# Sheet_1_2022-08-15.net
KiCad netlist of a schematic drawn in Altium Designer
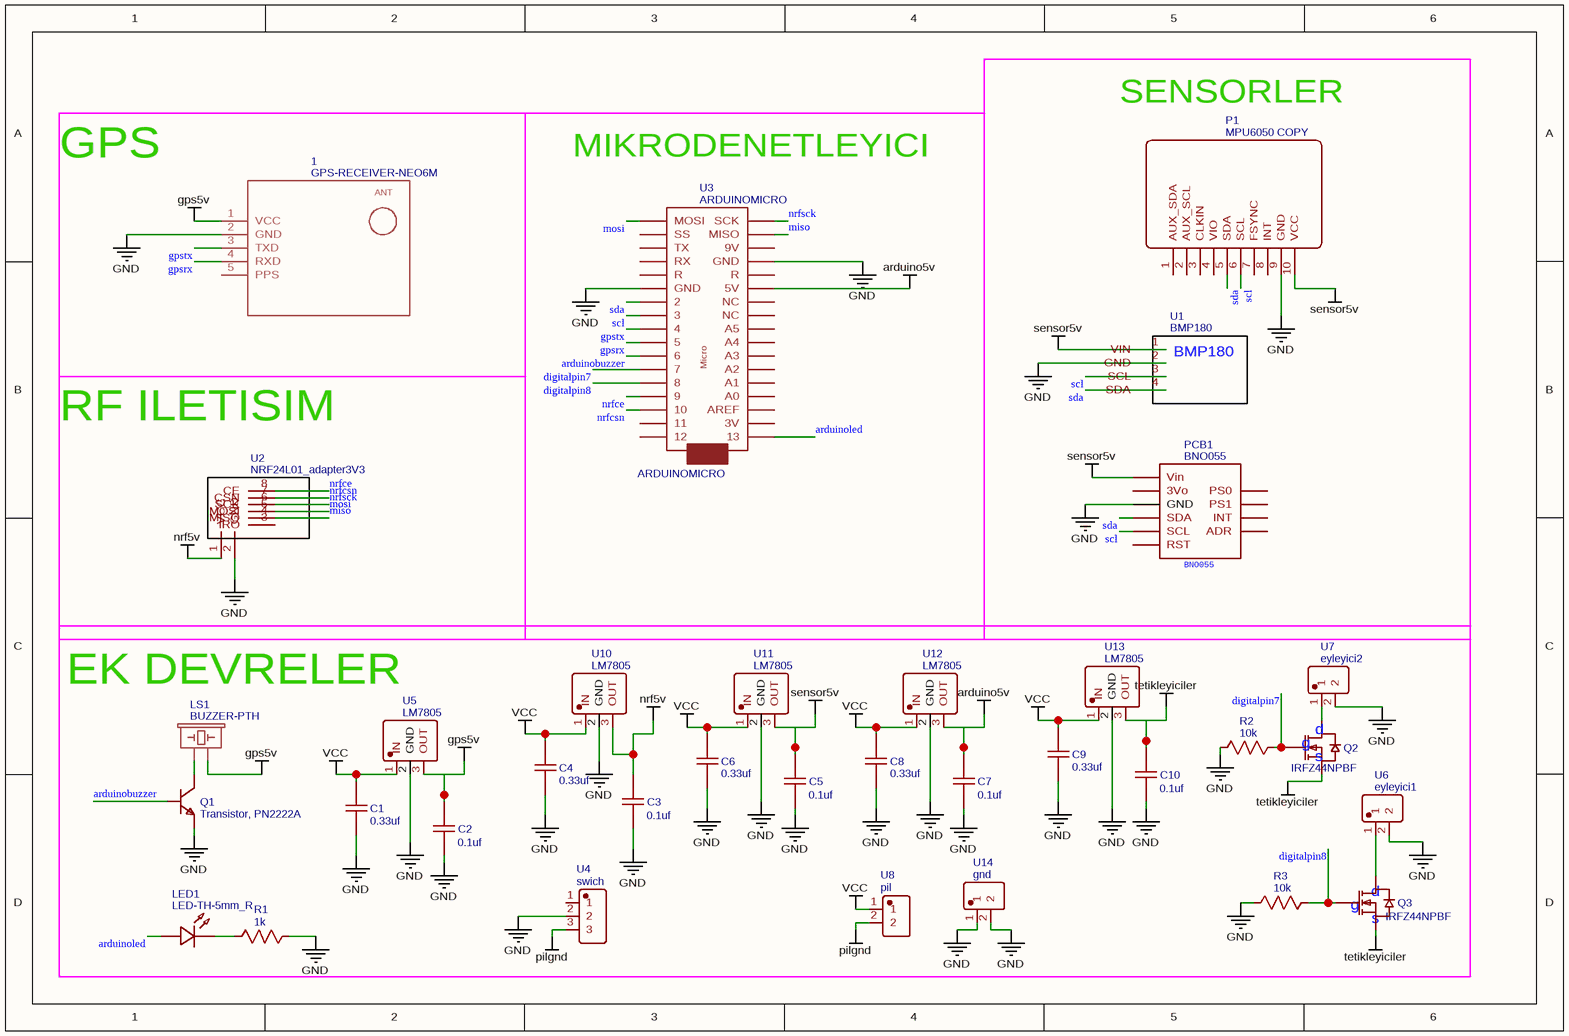
[diagram p0: Sheet_1_2022-08-15.schdoc]

(export (version "E")
  (design (tool "Eeschema 10.0.6"))
  (components
    (comp (ref "1")
      (value "GPS-RECEIVER-NEO6M")
      (fields (field (name "CONTRIBUTOR") "Otto Sonneveld"))
      (libsource (lib "altium-import") (part "root_0_GPS-RECEIVER-NEO6M_"))
    )
    (comp (ref "C1")
      (value "0.33uf")
      (fields (field (name "CONTRIBUTOR") "LCEDA_Lib"))
      (libsource (lib "altium-import") (part "root_1_0.33uf_"))
    )
    (comp (ref "C2")
      (value "0.1uf")
      (fields (field (name "CONTRIBUTOR") "LCEDA_Lib"))
      (libsource (lib "altium-import") (part "root_1_0.1uf_"))
    )
    (comp (ref "C3")
      (value "0.1uf")
      (fields (field (name "CONTRIBUTOR") "LCEDA_Lib"))
      (libsource (lib "altium-import") (part "root_1_0.1uf_"))
    )
    (comp (ref "C4")
      (value "0.33uf")
      (fields (field (name "CONTRIBUTOR") "LCEDA_Lib"))
      (libsource (lib "altium-import") (part "root_1_0.33uf_"))
    )
    (comp (ref "C5")
      (value "0.1uf")
      (fields (field (name "CONTRIBUTOR") "LCEDA_Lib"))
      (libsource (lib "altium-import") (part "root_1_0.1uf_"))
    )
    (comp (ref "C6")
      (value "0.33uf")
      (fields (field (name "CONTRIBUTOR") "LCEDA_Lib"))
      (libsource (lib "altium-import") (part "root_1_0.33uf_"))
    )
    (comp (ref "C7")
      (value "0.1uf")
      (fields (field (name "CONTRIBUTOR") "LCEDA_Lib"))
      (libsource (lib "altium-import") (part "root_1_0.1uf_"))
    )
    (comp (ref "C8")
      (value "0.33uf")
      (fields (field (name "CONTRIBUTOR") "LCEDA_Lib"))
      (libsource (lib "altium-import") (part "root_1_0.33uf_"))
    )
    (comp (ref "C9")
      (value "0.33uf")
      (fields (field (name "CONTRIBUTOR") "LCEDA_Lib"))
      (libsource (lib "altium-import") (part "root_1_0.33uf_"))
    )
    (comp (ref "C10")
      (value "0.1uf")
      (fields (field (name "CONTRIBUTOR") "LCEDA_Lib"))
      (libsource (lib "altium-import") (part "root_1_0.1uf_"))
    )
    (comp (ref "LED1")
      (value "LED-TH-5mm_R")
      (fields
        (field (name "BOM_MANUFACTURER PART") "333-2SURD/S530-A3")
        (field (name "BOM_SUPPLIER PART") "C87271")
        (field (name "CONTRIBUTOR") "LCEDA_Lib")
      )
      (libsource (lib "altium-import") (part "root_0_LED-TH-5mm_R_"))
    )
    (comp (ref "LS1")
      (value "BUZZER-PTH")
      (fields (field (name "CONTRIBUTOR") "Maxime Djouf"))
      (libsource (lib "altium-import") (part "root_0_BUZZER-PTH_"))
    )
    (comp (ref "P1") (value "MPU6050 COPY") (libsource (lib "altium-import") (part "root_0_MPU6050 COPY_")))
    (comp (ref "PCB1") (value "BNO055") (libsource (lib "altium-import") (part "root_0_BNO055_")))
    (comp (ref "Q1")
      (value "Transistor, PN2222A")
      (fields (field (name "BOM_MANUFACTURER PART") "PN2222A") (field (name "CONTRIBUTOR") "benjamin.nemec"))
      (libsource (lib "altium-import") (part "root_0_Transistor, PN2222A_"))
    )
    (comp (ref "Q2")
      (value "IRFZ44NPBF")
      (fields (field (name "BOM_SUPPLIER PART") "C2586"))
      (libsource (lib "altium-import") (part "root_0_IRFZ44NPBF_"))
    )
    (comp (ref "Q3")
      (value "IRFZ44NPBF")
      (fields (field (name "BOM_SUPPLIER PART") "C2586"))
      (libsource (lib "altium-import") (part "root_0_IRFZ44NPBF_"))
    )
    (comp (ref "R1")
      (value "1k")
      (fields (field (name "CONTRIBUTOR") "LCEDA_Lib"))
      (libsource (lib "altium-import") (part "root_0_1k_"))
    )
    (comp (ref "R2")
      (value "10k")
      (fields (field (name "CONTRIBUTOR") "LCEDA_Lib"))
      (libsource (lib "altium-import") (part "root_0_10k_"))
    )
    (comp (ref "R3")
      (value "10k")
      (fields (field (name "CONTRIBUTOR") "LCEDA_Lib"))
      (libsource (lib "altium-import") (part "root_0_10k_"))
    )
    (comp (ref "U1")
      (value "BMP180")
      (fields (field (name "CONTRIBUTOR") "delil1220"))
      (libsource (lib "altium-import") (part "root_0_BMP180_"))
    )
    (comp (ref "U2")
      (value "NRF24L01_adapter3V3")
      (fields (field (name "CONTRIBUTOR") "boonchuan khongsupsinsiri"))
      (libsource (lib "altium-import") (part "root_0_NRF24L01_adapter3V3_"))
    )
    (comp (ref "U3") (value "ARDUINOMICRO") (libsource (lib "altium-import") (part "root_1_ARDUINOMICRO_")))
    (comp (ref "U4")
      (value "swich")
      (fields (field (name "CONTRIBUTOR") "kenanbatur4"))
      (libsource (lib "altium-import") (part "root_0_swich_"))
    )
    (comp (ref "U5")
      (value "LM7805")
      (fields (field (name "BOM_SUPPLIER PART") "C845394") (field (name "CONTRIBUTOR") "LCSC"))
      (libsource (lib "altium-import") (part "root_1_LM7805_"))
    )
    (comp (ref "U6")
      (value "eyleyici1")
      (fields (field (name "CONTRIBUTOR") "kenanbatur"))
      (libsource (lib "altium-import") (part "root_1_eyleyici1_"))
    )
    (comp (ref "U7")
      (value "eyleyici2")
      (fields (field (name "CONTRIBUTOR") "kenanbatur"))
      (libsource (lib "altium-import") (part "root_1_eyleyici2_"))
    )
    (comp (ref "U8")
      (value "pil")
      (fields (field (name "CONTRIBUTOR") "kenanbatur"))
      (libsource (lib "altium-import") (part "root_0_pil_"))
    )
    (comp (ref "U10")
      (value "LM7805")
      (fields (field (name "BOM_SUPPLIER PART") "C845394") (field (name "CONTRIBUTOR") "LCSC"))
      (libsource (lib "altium-import") (part "root_1_LM7805_"))
    )
    (comp (ref "U11")
      (value "LM7805")
      (fields (field (name "BOM_SUPPLIER PART") "C845394") (field (name "CONTRIBUTOR") "LCSC"))
      (libsource (lib "altium-import") (part "root_1_LM7805_"))
    )
    (comp (ref "U12")
      (value "LM7805")
      (fields (field (name "BOM_SUPPLIER PART") "C845394") (field (name "CONTRIBUTOR") "LCSC"))
      (libsource (lib "altium-import") (part "root_1_LM7805_"))
    )
    (comp (ref "U13")
      (value "LM7805")
      (fields (field (name "BOM_SUPPLIER PART") "C845394") (field (name "CONTRIBUTOR") "LCSC"))
      (libsource (lib "altium-import") (part "root_1_LM7805_"))
    )
    (comp (ref "U14")
      (value "gnd")
      (fields (field (name "CONTRIBUTOR") "kenanbatur"))
      (libsource (lib "altium-import") (part "root_1_gnd_"))
    )
  )
  (nets
    (net (code "1") (name "/arduinobuzzer") (class "Default")
      (node (ref "Q1") (pin "2") (pinfunction "B_2") (pintype "passive"))
      (node (ref "U3") (pin "P$7") (pinfunction "6_P$7") (pintype "passive"))
    )
    (net (code "2") (name "/arduinoled") (class "Default")
      (node (ref "LED1") (pin "1") (pinfunction "1_1") (pintype "passive"))
      (node (ref "U3") (pin "P$34") (pinfunction "13_P$34") (pintype "passive"))
    )
    (net (code "3") (name "/digitalpin7") (class "Default")
      (node (ref "Q2") (pin "1") (pinfunction "G_1") (pintype "passive"))
      (node (ref "R2") (pin "2") (pinfunction "2_2") (pintype "passive"))
      (node (ref "U3") (pin "P$6") (pinfunction "7_P$6") (pintype "passive"))
    )
    (net (code "4") (name "/digitalpin8") (class "Default")
      (node (ref "Q3") (pin "1") (pinfunction "G_1") (pintype "passive"))
      (node (ref "R3") (pin "2") (pinfunction "2_2") (pintype "passive"))
      (node (ref "U3") (pin "P$5") (pinfunction "8_P$5") (pintype "passive"))
    )
    (net (code "5") (name "/gpsrx") (class "Default")
      (node (ref "1") (pin "4") (pinfunction "RXD_4") (pintype "passive"))
      (node (ref "U3") (pin "P$8") (pinfunction "5_P$8") (pintype "passive"))
    )
    (net (code "6") (name "/gpstx") (class "Default")
      (node (ref "1") (pin "3") (pinfunction "TXD_3") (pintype "passive"))
      (node (ref "U3") (pin "P$9") (pinfunction "4_P$9") (pintype "passive"))
    )
    (net (code "7") (name "/miso") (class "Default")
      (node (ref "U2") (pin "4") (pinfunction "MISO_4") (pintype "passive"))
      (node (ref "U3") (pin "P$19") (pinfunction "MISO_P$19") (pintype "passive"))
    )
    (net (code "8") (name "/mosi") (class "Default")
      (node (ref "U2") (pin "5") (pinfunction "MOSI_5") (pintype "passive"))
      (node (ref "U3") (pin "P$17") (pinfunction "MOSI_P$17") (pintype "passive"))
    )
    (net (code "9") (name "/nrfce") (class "Default")
      (node (ref "U2") (pin "8") (pinfunction "CE_8") (pintype "passive"))
      (node (ref "U3") (pin "P$4") (pinfunction "9_P$4") (pintype "passive"))
    )
    (net (code "10") (name "/nrfcsn") (class "Default")
      (node (ref "U2") (pin "7") (pinfunction "CSN_7") (pintype "passive"))
      (node (ref "U3") (pin "P$3") (pinfunction "10_P$3") (pintype "passive"))
    )
    (net (code "11") (name "/nrfsck") (class "Default")
      (node (ref "U2") (pin "6") (pinfunction "SCK_6") (pintype "passive"))
      (node (ref "U3") (pin "P$18") (pinfunction "SCK_P$18") (pintype "passive"))
    )
    (net (code "12") (name "/scl") (class "Default")
      (node (ref "P1") (pin "6") (pinfunction "SCL_6") (pintype "passive"))
      (node (ref "PCB1") (pin "5") (pinfunction "SCL_5") (pintype "passive"))
      (node (ref "U1") (pin "3") (pinfunction "SCL_3") (pintype "passive"))
      (node (ref "U3") (pin "P$10") (pinfunction "3_P$10") (pintype "passive"))
    )
    (net (code "13") (name "/sda") (class "Default")
      (node (ref "P1") (pin "5") (pinfunction "SDA_5") (pintype "passive"))
      (node (ref "PCB1") (pin "4") (pinfunction "SDA_4") (pintype "passive"))
      (node (ref "U1") (pin "4") (pinfunction "SDA_4") (pintype "passive"))
      (node (ref "U3") (pin "P$11") (pinfunction "2_P$11") (pintype "passive"))
    )
    (net (code "14") (name "GND") (class "Default")
      (node (ref "1") (pin "2") (pinfunction "GND_2") (pintype "passive"))
      (node (ref "C1") (pin "1") (pinfunction "1_1") (pintype "passive"))
      (node (ref "C10") (pin "1") (pinfunction "1_1") (pintype "passive"))
      (node (ref "C2") (pin "1") (pinfunction "1_1") (pintype "passive"))
      (node (ref "C3") (pin "1") (pinfunction "1_1") (pintype "passive"))
      (node (ref "C4") (pin "1") (pinfunction "1_1") (pintype "passive"))
      (node (ref "C5") (pin "1") (pinfunction "1_1") (pintype "passive"))
      (node (ref "C6") (pin "1") (pinfunction "1_1") (pintype "passive"))
      (node (ref "C7") (pin "1") (pinfunction "1_1") (pintype "passive"))
      (node (ref "C8") (pin "1") (pinfunction "1_1") (pintype "passive"))
      (node (ref "C9") (pin "1") (pinfunction "1_1") (pintype "passive"))
      (node (ref "P1") (pin "9") (pinfunction "GND_9") (pintype "passive"))
      (node (ref "PCB1") (pin "3") (pinfunction "GND_3") (pintype "passive"))
      (node (ref "Q1") (pin "1") (pinfunction "E_1") (pintype "passive"))
      (node (ref "R1") (pin "2") (pinfunction "2_2") (pintype "passive"))
      (node (ref "R2") (pin "1") (pinfunction "1_1") (pintype "passive"))
      (node (ref "R3") (pin "1") (pinfunction "1_1") (pintype "passive"))
      (node (ref "U1") (pin "2") (pinfunction "GND_2") (pintype "passive"))
      (node (ref "U10") (pin "2") (pinfunction "GND_2") (pintype "passive"))
      (node (ref "U11") (pin "2") (pinfunction "GND_2") (pintype "passive"))
      (node (ref "U12") (pin "2") (pinfunction "GND_2") (pintype "passive"))
      (node (ref "U13") (pin "2") (pinfunction "GND_2") (pintype "passive"))
      (node (ref "U14") (pin "1") (pinfunction "1_1") (pintype "passive"))
      (node (ref "U14") (pin "2") (pinfunction "2_2") (pintype "passive"))
      (node (ref "U2") (pin "2") (pinfunction "GND_2") (pintype "passive"))
      (node (ref "U3") (pin "P$12") (pinfunction "GND_P$12") (pintype "passive"))
      (node (ref "U3") (pin "P$21") (pinfunction "GND_P$21") (pintype "passive"))
      (node (ref "U4") (pin "2") (pinfunction "2_2") (pintype "passive"))
      (node (ref "U5") (pin "2") (pinfunction "GND_2") (pintype "passive"))
      (node (ref "U6") (pin "2") (pinfunction "2_2") (pintype "passive"))
      (node (ref "U7") (pin "2") (pinfunction "2_2") (pintype "passive"))
    )
    (net (code "15") (name "Net-(LED1-Pad2)") (class "Default")
      (node (ref "LED1") (pin "2") (pinfunction "2_2") (pintype "passive"))
      (node (ref "R1") (pin "1") (pinfunction "1_1") (pintype "passive"))
    )
    (net (code "16") (name "Net-(LS1-1)") (class "Default")
      (node (ref "LS1") (pin "+") (pinfunction "1_+") (pintype "passive"))
      (node (ref "Q1") (pin "3") (pinfunction "C_3") (pintype "passive"))
    )
    (net (code "17") (name "Net-(Q2-D)") (class "Default")
      (node (ref "Q2") (pin "2") (pinfunction "D_2") (pintype "passive"))
      (node (ref "U7") (pin "1") (pinfunction "1_1") (pintype "passive"))
    )
    (net (code "18") (name "Net-(Q3-D)") (class "Default")
      (node (ref "Q3") (pin "2") (pinfunction "D_2") (pintype "passive"))
      (node (ref "U6") (pin "1") (pinfunction "1_1") (pintype "passive"))
    )
    (net (code "19") (name "VCC") (class "Default")
      (node (ref "C1") (pin "2") (pinfunction "2_2") (pintype "passive"))
      (node (ref "C4") (pin "2") (pinfunction "2_2") (pintype "passive"))
      (node (ref "C6") (pin "2") (pinfunction "2_2") (pintype "passive"))
      (node (ref "C8") (pin "2") (pinfunction "2_2") (pintype "passive"))
      (node (ref "C9") (pin "2") (pinfunction "2_2") (pintype "passive"))
      (node (ref "U10") (pin "1") (pinfunction "IN_1") (pintype "passive"))
      (node (ref "U11") (pin "1") (pinfunction "IN_1") (pintype "passive"))
      (node (ref "U12") (pin "1") (pinfunction "IN_1") (pintype "passive"))
      (node (ref "U13") (pin "1") (pinfunction "IN_1") (pintype "passive"))
      (node (ref "U5") (pin "1") (pinfunction "IN_1") (pintype "passive"))
      (node (ref "U8") (pin "1") (pinfunction "1_1") (pintype "passive"))
    )
    (net (code "20") (name "arduino5v") (class "Default")
      (node (ref "C7") (pin "2") (pinfunction "2_2") (pintype "passive"))
      (node (ref "U12") (pin "3") (pinfunction "OUT_3") (pintype "passive"))
      (node (ref "U3") (pin "P$23") (pinfunction "5V_P$23") (pintype "passive"))
    )
    (net (code "21") (name "gps5v") (class "Default")
      (node (ref "1") (pin "1") (pinfunction "VCC_1") (pintype "passive"))
      (node (ref "C2") (pin "2") (pinfunction "2_2") (pintype "passive"))
      (node (ref "LS1") (pin "-") (pinfunction "2_-") (pintype "passive"))
      (node (ref "U5") (pin "3") (pinfunction "OUT_3") (pintype "passive"))
    )
    (net (code "22") (name "nrf5v") (class "Default")
      (node (ref "C3") (pin "2") (pinfunction "2_2") (pintype "passive"))
      (node (ref "U10") (pin "3") (pinfunction "OUT_3") (pintype "passive"))
      (node (ref "U2") (pin "1") (pinfunction "VCC_1") (pintype "passive"))
    )
    (net (code "23") (name "pilgnd") (class "Default")
      (node (ref "U4") (pin "3") (pinfunction "3_3") (pintype "passive"))
      (node (ref "U8") (pin "2") (pinfunction "2_2") (pintype "passive"))
    )
    (net (code "24") (name "sensor5v") (class "Default")
      (node (ref "C5") (pin "2") (pinfunction "2_2") (pintype "passive"))
      (node (ref "P1") (pin "10") (pinfunction "VCC_10") (pintype "passive"))
      (node (ref "PCB1") (pin "1") (pinfunction "Vin_1") (pintype "passive"))
      (node (ref "U1") (pin "1") (pinfunction "VIN_1") (pintype "passive"))
      (node (ref "U11") (pin "3") (pinfunction "OUT_3") (pintype "passive"))
    )
    (net (code "25") (name "tetikleyiciler") (class "Default")
      (node (ref "C10") (pin "2") (pinfunction "2_2") (pintype "passive"))
      (node (ref "Q2") (pin "3") (pinfunction "S_3") (pintype "passive"))
      (node (ref "Q3") (pin "3") (pinfunction "S_3") (pintype "passive"))
      (node (ref "U13") (pin "3") (pinfunction "OUT_3") (pintype "passive"))
    )
    (net (code "26") (name "unconnected-(1-PPS-Pad5)") (class "Default")
      (node (ref "1") (pin "5") (pinfunction "PPS_5") (pintype "passive"))
    )
    (net (code "27") (name "unconnected-(P1-AUX_SCL-Pad2)") (class "Default")
      (node (ref "P1") (pin "2") (pinfunction "AUX_SCL_2") (pintype "passive"))
    )
    (net (code "28") (name "unconnected-(P1-AUX_SDA-Pad1)") (class "Default")
      (node (ref "P1") (pin "1") (pinfunction "AUX_SDA_1") (pintype "passive"))
    )
    (net (code "29") (name "unconnected-(P1-CLKIN-Pad3)") (class "Default")
      (node (ref "P1") (pin "3") (pinfunction "CLKIN_3") (pintype "passive"))
    )
    (net (code "30") (name "unconnected-(P1-FSYNC-Pad7)") (class "Default")
      (node (ref "P1") (pin "7") (pinfunction "FSYNC_7") (pintype "passive"))
    )
    (net (code "31") (name "unconnected-(P1-INT-Pad8)") (class "Default")
      (node (ref "P1") (pin "8") (pinfunction "INT_8") (pintype "passive"))
    )
    (net (code "32") (name "unconnected-(P1-VIO-Pad4)") (class "Default")
      (node (ref "P1") (pin "4") (pinfunction "VIO_4") (pintype "passive"))
    )
    (net (code "33") (name "unconnected-(PCB1-3Vo-Pad2)") (class "Default")
      (node (ref "PCB1") (pin "2") (pinfunction "3Vo_2") (pintype "passive"))
    )
    (net (code "34") (name "unconnected-(PCB1-ADR-Pad10)") (class "Default")
      (node (ref "PCB1") (pin "10") (pinfunction "ADR_10") (pintype "passive"))
    )
    (net (code "35") (name "unconnected-(PCB1-INT-Pad9)") (class "Default")
      (node (ref "PCB1") (pin "9") (pinfunction "INT_9") (pintype "passive"))
    )
    (net (code "36") (name "unconnected-(PCB1-PS0-Pad7)") (class "Default")
      (node (ref "PCB1") (pin "7") (pinfunction "PS0_7") (pintype "passive"))
    )
    (net (code "37") (name "unconnected-(PCB1-PS1-Pad8)") (class "Default")
      (node (ref "PCB1") (pin "8") (pinfunction "PS1_8") (pintype "passive"))
    )
    (net (code "38") (name "unconnected-(PCB1-RST-Pad6)") (class "Default")
      (node (ref "PCB1") (pin "6") (pinfunction "RST_6") (pintype "passive"))
    )
    (net (code "39") (name "unconnected-(U2-IRO-Pad3)") (class "Default")
      (node (ref "U2") (pin "3") (pinfunction "IRO_3") (pintype "passive"))
    )
    (net (code "40") (name "unconnected-(U3-3V-PadP$33)") (class "Default")
      (node (ref "U3") (pin "P$33") (pinfunction "3V_P$33") (pintype "passive"))
    )
    (net (code "41") (name "unconnected-(U3-9V-PadP$20)") (class "Default")
      (node (ref "U3") (pin "P$20") (pinfunction "9V_P$20") (pintype "passive"))
    )
    (net (code "42") (name "unconnected-(U3-11-PadP$2)") (class "Default")
      (node (ref "U3") (pin "P$2") (pinfunction "11_P$2") (pintype "passive"))
    )
    (net (code "43") (name "unconnected-(U3-12-PadP$1)") (class "Default")
      (node (ref "U3") (pin "P$1") (pinfunction "12_P$1") (pintype "passive"))
    )
    (net (code "44") (name "unconnected-(U3-A0-PadP$31)") (class "Default")
      (node (ref "U3") (pin "P$31") (pinfunction "A0_P$31") (pintype "passive"))
    )
    (net (code "45") (name "unconnected-(U3-A1-PadP$30)") (class "Default")
      (node (ref "U3") (pin "P$30") (pinfunction "A1_P$30") (pintype "passive"))
    )
    (net (code "46") (name "unconnected-(U3-A2-PadP$29)") (class "Default")
      (node (ref "U3") (pin "P$29") (pinfunction "A2_P$29") (pintype "passive"))
    )
    (net (code "47") (name "unconnected-(U3-A3-PadP$28)") (class "Default")
      (node (ref "U3") (pin "P$28") (pinfunction "A3_P$28") (pintype "passive"))
    )
    (net (code "48") (name "unconnected-(U3-A4-PadP$27)") (class "Default")
      (node (ref "U3") (pin "P$27") (pinfunction "A4_P$27") (pintype "passive"))
    )
    (net (code "49") (name "unconnected-(U3-A5-PadP$26)") (class "Default")
      (node (ref "U3") (pin "P$26") (pinfunction "A5_P$26") (pintype "passive"))
    )
    (net (code "50") (name "unconnected-(U3-AREF-PadP$32)") (class "Default")
      (node (ref "U3") (pin "P$32") (pinfunction "AREF_P$32") (pintype "passive"))
    )
    (net (code "51") (name "unconnected-(U3-NC-PadP$24)") (class "Default")
      (node (ref "U3") (pin "P$24") (pinfunction "NC_P$24") (pintype "passive"))
    )
    (net (code "52") (name "unconnected-(U3-NC-PadP$25)") (class "Default")
      (node (ref "U3") (pin "P$25") (pinfunction "NC_P$25") (pintype "passive"))
    )
    (net (code "53") (name "unconnected-(U3-R-PadP$13)") (class "Default")
      (node (ref "U3") (pin "P$13") (pinfunction "R_P$13") (pintype "passive"))
    )
    (net (code "54") (name "unconnected-(U3-R-PadP$22)") (class "Default")
      (node (ref "U3") (pin "P$22") (pinfunction "R_P$22") (pintype "passive"))
    )
    (net (code "55") (name "unconnected-(U3-RX-PadP$14)") (class "Default")
      (node (ref "U3") (pin "P$14") (pinfunction "RX_P$14") (pintype "passive"))
    )
    (net (code "56") (name "unconnected-(U3-SS-PadP$16)") (class "Default")
      (node (ref "U3") (pin "P$16") (pinfunction "SS_P$16") (pintype "passive"))
    )
    (net (code "57") (name "unconnected-(U3-TX-PadP$15)") (class "Default")
      (node (ref "U3") (pin "P$15") (pinfunction "TX_P$15") (pintype "passive"))
    )
    (net (code "58") (name "unconnected-(U4-Pad1)") (class "Default")
      (node (ref "U4") (pin "1") (pinfunction "1_1") (pintype "passive"))
    )
  )
)
